# Temp_WiFi.net
KiCad netlist of a schematic drawn in EAGLE
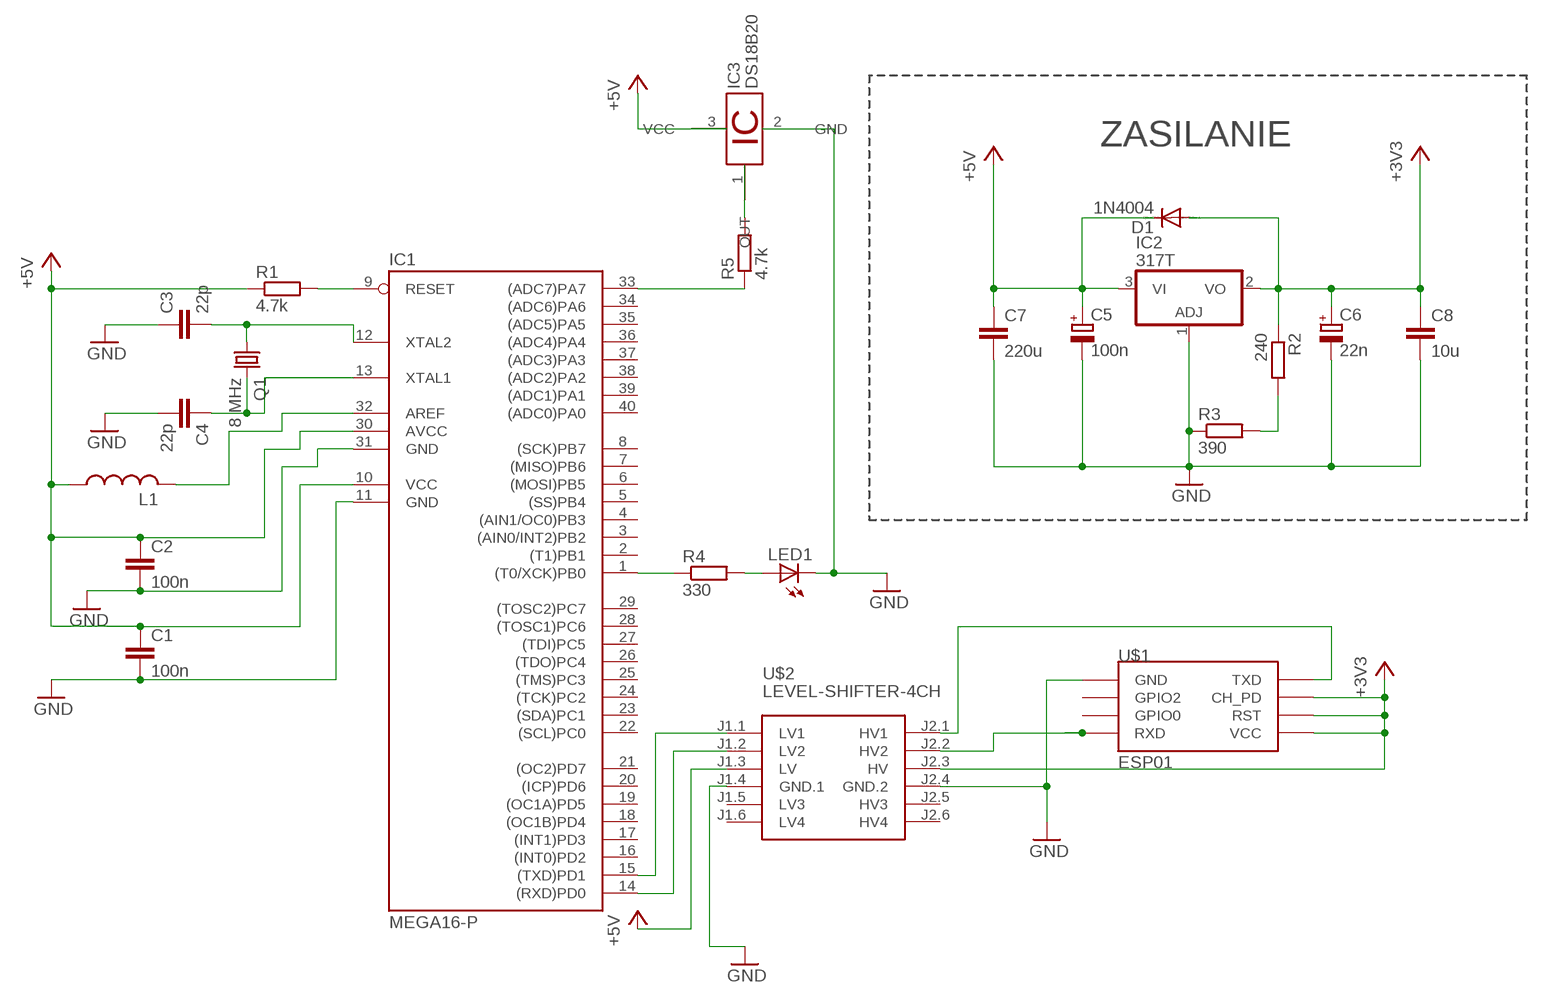
[diagram p0: schematic, sheet 1]

(export (version "E")
  (design (tool "Eeschema 10.0.6"))
  (components
    (comp (ref "C1")
      (value "100n")
      (footprint "eagle-import:C025-040X050")
      (libsource (lib "eagle-import") (part "C-EU025-040X050"))
    )
    (comp (ref "C2")
      (value "100n")
      (footprint "eagle-import:C025-040X050")
      (libsource (lib "eagle-import") (part "C-EU025-040X050"))
    )
    (comp (ref "C3")
      (value "22p")
      (footprint "eagle-import:C025-040X050")
      (libsource (lib "eagle-import") (part "C-EU025-040X050"))
    )
    (comp (ref "C4")
      (value "22p")
      (footprint "eagle-import:C025-040X050")
      (libsource (lib "eagle-import") (part "C-EU025-040X050"))
    )
    (comp (ref "C5")
      (value "100n")
      (footprint "eagle-import:E7,5-16")
      (libsource (lib "eagle-import") (part "CPOL-EUE7.5-16"))
    )
    (comp (ref "C6")
      (value "22n")
      (footprint "eagle-import:E7,5-16")
      (libsource (lib "eagle-import") (part "CPOL-EUE7.5-16"))
    )
    (comp (ref "C7")
      (value "220u")
      (footprint "eagle-import:C025-030X050")
      (libsource (lib "eagle-import") (part "C-EU025-030X050"))
    )
    (comp (ref "C8")
      (value "10u")
      (footprint "eagle-import:C025-030X050")
      (libsource (lib "eagle-import") (part "C-EU025-030X050"))
    )
    (comp (ref "D1")
      (value "1N4004")
      (footprint "eagle-import:DO41-10")
      (libsource (lib "eagle-import") (part "1N4004"))
    )
    (comp (ref "IC1")
      (value "MEGA16-P")
      (footprint "eagle-import:DIL40")
      (fields (field (name "MPN") "ATMEGA16-16PU"))
      (libsource (lib "eagle-import") (part "MEGA16-P"))
    )
    (comp (ref "IC2")
      (value "317T")
      (footprint "eagle-import:TO220H")
      (libsource (lib "eagle-import") (part "317T"))
    )
    (comp (ref "IC3")
      (value "DS18B20")
      (footprint "eagle-import:TO92-")
      (libsource (lib "eagle-import") (part "DS18B20"))
    )
    (comp (ref "L1")
      (value "L-US0204/7")
      (footprint "eagle-import:0204_7")
      (libsource (lib "eagle-import") (part "L-US0204/7"))
    )
    (comp (ref "LED1")
      (value "LED5MM")
      (footprint "eagle-import:LED5MM")
      (libsource (lib "eagle-import") (part "LED5MM"))
    )
    (comp (ref "Q1")
      (value "8 MHz")
      (footprint "eagle-import:HC49U-V")
      (libsource (lib "eagle-import") (part "CRYSTALHC49U-V"))
    )
    (comp (ref "R1")
      (value "4.7k")
      (footprint "eagle-import:0204_7")
      (libsource (lib "eagle-import") (part "R-EU_0204/7"))
    )
    (comp (ref "R2")
      (value "240")
      (footprint "eagle-import:0204_7")
      (libsource (lib "eagle-import") (part "R-EU_0204/7"))
    )
    (comp (ref "R3")
      (value "390")
      (footprint "eagle-import:0204_7")
      (libsource (lib "eagle-import") (part "R-EU_0204/7"))
    )
    (comp (ref "R4")
      (value "330")
      (footprint "eagle-import:0204_7")
      (libsource (lib "eagle-import") (part "R-EU_0204/7"))
    )
    (comp (ref "R5")
      (value "4.7k")
      (footprint "eagle-import:0204_7")
      (libsource (lib "eagle-import") (part "R-EU_0204/7"))
    )
    (comp (ref "U$1")
      (value "ESP01")
      (footprint "eagle-import:ESP01")
      (libsource (lib "eagle-import") (part "ESP01"))
    )
    (comp (ref "U$2")
      (value "LEVEL-SHIFTER-4CH")
      (footprint "eagle-import:LEVEL-SHIFTER-4CH")
      (libsource (lib "eagle-import") (part "LEVEL-SHIFTER-4CH"))
    )
  )
  (nets
    (net (code "1") (name "+3V3") (class "Default")
      (node (ref "C6") (pin "+") (pinfunction "+_+") (pintype "passive"))
      (node (ref "C8") (pin "1") (pinfunction "1_1") (pintype "passive"))
      (node (ref "D1") (pin "A") (pinfunction "A_A") (pintype "passive"))
      (node (ref "IC2") (pin "2") (pinfunction "VO_2") (pintype "passive"))
      (node (ref "R2") (pin "1") (pinfunction "1_1") (pintype "passive"))
      (node (ref "U$1") (pin "CH_PD") (pinfunction "CH_PD_CH_PD") (pintype "bidirectional"))
      (node (ref "U$1") (pin "RST") (pinfunction "RST_RST") (pintype "bidirectional"))
      (node (ref "U$1") (pin "VCC") (pinfunction "VCC_VCC") (pintype "bidirectional"))
      (node (ref "U$2") (pin "J2.3") (pinfunction "HV_J2.3") (pintype "power_in"))
    )
    (net (code "2") (name "+5V") (class "Default")
      (node (ref "C1") (pin "1") (pinfunction "1_1") (pintype "passive"))
      (node (ref "C2") (pin "1") (pinfunction "1_1") (pintype "passive"))
      (node (ref "C5") (pin "+") (pinfunction "+_+") (pintype "passive"))
      (node (ref "C7") (pin "1") (pinfunction "1_1") (pintype "passive"))
      (node (ref "D1") (pin "C") (pinfunction "C_C") (pintype "passive"))
      (node (ref "IC1") (pin "10") (pinfunction "VCC_10") (pintype "power_in"))
      (node (ref "IC1") (pin "30") (pinfunction "AVCC_30") (pintype "power_in"))
      (node (ref "IC2") (pin "3") (pinfunction "VI_3") (pintype "input"))
      (node (ref "IC3") (pin "3") (pinfunction "VCC_3") (pintype "bidirectional"))
      (node (ref "L1") (pin "1") (pinfunction "1_1") (pintype "passive"))
      (node (ref "R1") (pin "1") (pinfunction "1_1") (pintype "passive"))
      (node (ref "U$2") (pin "J1.3") (pinfunction "LV_J1.3") (pintype "power_in"))
    )
    (net (code "3") (name "/XTAL2") (class "Default")
      (node (ref "C3") (pin "2") (pinfunction "2_2") (pintype "passive"))
      (node (ref "C4") (pin "1") (pinfunction "1_1") (pintype "passive"))
      (node (ref "IC1") (pin "12") (pinfunction "XTAL2_12") (pintype "bidirectional"))
      (node (ref "IC1") (pin "13") (pinfunction "XTAL1_13") (pintype "bidirectional"))
      (node (ref "Q1") (pin "1") (pinfunction "1_1") (pintype "passive"))
      (node (ref "Q1") (pin "2") (pinfunction "2_2") (pintype "passive"))
    )
    (net (code "4") (name "GND") (class "Default")
      (node (ref "C1") (pin "2") (pinfunction "2_2") (pintype "passive"))
      (node (ref "C2") (pin "2") (pinfunction "2_2") (pintype "passive"))
      (node (ref "C3") (pin "1") (pinfunction "1_1") (pintype "passive"))
      (node (ref "C4") (pin "2") (pinfunction "2_2") (pintype "passive"))
      (node (ref "C5") (pin "-") (pinfunction "-_-") (pintype "passive"))
      (node (ref "C6") (pin "-") (pinfunction "-_-") (pintype "passive"))
      (node (ref "C7") (pin "2") (pinfunction "2_2") (pintype "passive"))
      (node (ref "C8") (pin "2") (pinfunction "2_2") (pintype "passive"))
      (node (ref "IC1") (pin "11") (pinfunction "GND_11") (pintype "power_in"))
      (node (ref "IC1") (pin "31") (pinfunction "GND_31") (pintype "power_in"))
      (node (ref "IC2") (pin "1") (pinfunction "ADJ_1") (pintype "input"))
      (node (ref "IC3") (pin "2") (pinfunction "GND_2") (pintype "bidirectional"))
      (node (ref "LED1") (pin "K") (pinfunction "C_K") (pintype "passive"))
      (node (ref "R3") (pin "1") (pinfunction "1_1") (pintype "passive"))
      (node (ref "U$1") (pin "GND") (pinfunction "GND_GND") (pintype "bidirectional"))
      (node (ref "U$2") (pin "J1.4") (pinfunction "GND.1_J1.4") (pintype "power_in"))
      (node (ref "U$2") (pin "J2.4") (pinfunction "GND.2_J2.4") (pintype "power_in"))
    )
    (net (code "5") (name "Net-(IC1-(ADC7)PA7)") (class "Default")
      (node (ref "IC1") (pin "33") (pinfunction "(ADC7)PA7_33") (pintype "bidirectional"))
      (node (ref "R5") (pin "1") (pinfunction "1_1") (pintype "passive"))
    )
    (net (code "6") (name "Net-(IC1-(RXD)PD0)") (class "Default")
      (node (ref "IC1") (pin "14") (pinfunction "(RXD)PD0_14") (pintype "bidirectional"))
      (node (ref "U$2") (pin "J1.2") (pinfunction "LV2_J1.2") (pintype "bidirectional"))
    )
    (net (code "7") (name "Net-(IC1-(T0{slash}XCK)PB0)") (class "Default")
      (node (ref "IC1") (pin "1") (pinfunction "(T0/XCK)PB0_1") (pintype "bidirectional"))
      (node (ref "R4") (pin "1") (pinfunction "1_1") (pintype "passive"))
    )
    (net (code "8") (name "Net-(IC1-(TXD)PD1)") (class "Default")
      (node (ref "IC1") (pin "15") (pinfunction "(TXD)PD1_15") (pintype "bidirectional"))
      (node (ref "U$2") (pin "J1.1") (pinfunction "LV1_J1.1") (pintype "bidirectional"))
    )
    (net (code "9") (name "Net-(IC1-AREF)") (class "Default")
      (node (ref "IC1") (pin "32") (pinfunction "AREF_32") (pintype "passive"))
      (node (ref "L1") (pin "2") (pinfunction "2_2") (pintype "passive"))
    )
    (net (code "10") (name "Net-(IC1-RESET)") (class "Default")
      (node (ref "IC1") (pin "9") (pinfunction "RESET_9") (pintype "input"))
      (node (ref "R1") (pin "2") (pinfunction "2_2") (pintype "passive"))
    )
    (net (code "11") (name "Net-(IC3-OUT)") (class "Default")
      (node (ref "IC3") (pin "1") (pinfunction "OUT_1") (pintype "bidirectional"))
      (node (ref "R5") (pin "2") (pinfunction "2_2") (pintype "passive"))
    )
    (net (code "12") (name "Net-(LED1-PadA)") (class "Default")
      (node (ref "LED1") (pin "A") (pinfunction "A_A") (pintype "passive"))
      (node (ref "R4") (pin "2") (pinfunction "2_2") (pintype "passive"))
    )
    (net (code "13") (name "Net-(R2-Pad2)") (class "Default")
      (node (ref "R2") (pin "2") (pinfunction "2_2") (pintype "passive"))
      (node (ref "R3") (pin "2") (pinfunction "2_2") (pintype "passive"))
    )
    (net (code "14") (name "Net-(U$1-RXD)") (class "Default")
      (node (ref "U$1") (pin "RX") (pinfunction "RXD_RX") (pintype "bidirectional"))
      (node (ref "U$2") (pin "J2.2") (pinfunction "HV2_J2.2") (pintype "bidirectional"))
    )
    (net (code "15") (name "Net-(U$1-TXD)") (class "Default")
      (node (ref "U$1") (pin "TX") (pinfunction "TXD_TX") (pintype "bidirectional"))
      (node (ref "U$2") (pin "J2.1") (pinfunction "HV1_J2.1") (pintype "bidirectional"))
    )
    (net (code "16") (name "unconnected-(IC1-(ADC0)PA0-Pad40)") (class "Default")
      (node (ref "IC1") (pin "40") (pinfunction "(ADC0)PA0_40") (pintype "bidirectional"))
    )
    (net (code "17") (name "unconnected-(IC1-(ADC1)PA1-Pad39)") (class "Default")
      (node (ref "IC1") (pin "39") (pinfunction "(ADC1)PA1_39") (pintype "bidirectional"))
    )
    (net (code "18") (name "unconnected-(IC1-(ADC2)PA2-Pad38)") (class "Default")
      (node (ref "IC1") (pin "38") (pinfunction "(ADC2)PA2_38") (pintype "bidirectional"))
    )
    (net (code "19") (name "unconnected-(IC1-(ADC3)PA3-Pad37)") (class "Default")
      (node (ref "IC1") (pin "37") (pinfunction "(ADC3)PA3_37") (pintype "bidirectional"))
    )
    (net (code "20") (name "unconnected-(IC1-(ADC4)PA4-Pad36)") (class "Default")
      (node (ref "IC1") (pin "36") (pinfunction "(ADC4)PA4_36") (pintype "bidirectional"))
    )
    (net (code "21") (name "unconnected-(IC1-(ADC5)PA5-Pad35)") (class "Default")
      (node (ref "IC1") (pin "35") (pinfunction "(ADC5)PA5_35") (pintype "bidirectional"))
    )
    (net (code "22") (name "unconnected-(IC1-(ADC6)PA6-Pad34)") (class "Default")
      (node (ref "IC1") (pin "34") (pinfunction "(ADC6)PA6_34") (pintype "bidirectional"))
    )
    (net (code "23") (name "unconnected-(IC1-(AIN0{slash}INT2)PB2-Pad3)") (class "Default")
      (node (ref "IC1") (pin "3") (pinfunction "(AIN0/INT2)PB2_3") (pintype "bidirectional"))
    )
    (net (code "24") (name "unconnected-(IC1-(AIN1{slash}OC0)PB3-Pad4)") (class "Default")
      (node (ref "IC1") (pin "4") (pinfunction "(AIN1/OC0)PB3_4") (pintype "bidirectional"))
    )
    (net (code "25") (name "unconnected-(IC1-(ICP)PD6-Pad20)") (class "Default")
      (node (ref "IC1") (pin "20") (pinfunction "(ICP)PD6_20") (pintype "bidirectional"))
    )
    (net (code "26") (name "unconnected-(IC1-(INT0)PD2-Pad16)") (class "Default")
      (node (ref "IC1") (pin "16") (pinfunction "(INT0)PD2_16") (pintype "bidirectional"))
    )
    (net (code "27") (name "unconnected-(IC1-(INT1)PD3-Pad17)") (class "Default")
      (node (ref "IC1") (pin "17") (pinfunction "(INT1)PD3_17") (pintype "bidirectional"))
    )
    (net (code "28") (name "unconnected-(IC1-(MISO)PB6-Pad7)") (class "Default")
      (node (ref "IC1") (pin "7") (pinfunction "(MISO)PB6_7") (pintype "bidirectional"))
    )
    (net (code "29") (name "unconnected-(IC1-(MOSI)PB5-Pad6)") (class "Default")
      (node (ref "IC1") (pin "6") (pinfunction "(MOSI)PB5_6") (pintype "bidirectional"))
    )
    (net (code "30") (name "unconnected-(IC1-(OC1A)PD5-Pad19)") (class "Default")
      (node (ref "IC1") (pin "19") (pinfunction "(OC1A)PD5_19") (pintype "bidirectional"))
    )
    (net (code "31") (name "unconnected-(IC1-(OC1B)PD4-Pad18)") (class "Default")
      (node (ref "IC1") (pin "18") (pinfunction "(OC1B)PD4_18") (pintype "bidirectional"))
    )
    (net (code "32") (name "unconnected-(IC1-(OC2)PD7-Pad21)") (class "Default")
      (node (ref "IC1") (pin "21") (pinfunction "(OC2)PD7_21") (pintype "bidirectional"))
    )
    (net (code "33") (name "unconnected-(IC1-(SCK)PB7-Pad8)") (class "Default")
      (node (ref "IC1") (pin "8") (pinfunction "(SCK)PB7_8") (pintype "bidirectional"))
    )
    (net (code "34") (name "unconnected-(IC1-(SCL)PC0-Pad22)") (class "Default")
      (node (ref "IC1") (pin "22") (pinfunction "(SCL)PC0_22") (pintype "bidirectional"))
    )
    (net (code "35") (name "unconnected-(IC1-(SDA)PC1-Pad23)") (class "Default")
      (node (ref "IC1") (pin "23") (pinfunction "(SDA)PC1_23") (pintype "bidirectional"))
    )
    (net (code "36") (name "unconnected-(IC1-(SS)PB4-Pad5)") (class "Default")
      (node (ref "IC1") (pin "5") (pinfunction "(SS)PB4_5") (pintype "bidirectional"))
    )
    (net (code "37") (name "unconnected-(IC1-(T1)PB1-Pad2)") (class "Default")
      (node (ref "IC1") (pin "2") (pinfunction "(T1)PB1_2") (pintype "bidirectional"))
    )
    (net (code "38") (name "unconnected-(IC1-(TCK)PC2-Pad24)") (class "Default")
      (node (ref "IC1") (pin "24") (pinfunction "(TCK)PC2_24") (pintype "bidirectional"))
    )
    (net (code "39") (name "unconnected-(IC1-(TDI)PC5-Pad27)") (class "Default")
      (node (ref "IC1") (pin "27") (pinfunction "(TDI)PC5_27") (pintype "bidirectional"))
    )
    (net (code "40") (name "unconnected-(IC1-(TDO)PC4-Pad26)") (class "Default")
      (node (ref "IC1") (pin "26") (pinfunction "(TDO)PC4_26") (pintype "bidirectional"))
    )
    (net (code "41") (name "unconnected-(IC1-(TMS)PC3-Pad25)") (class "Default")
      (node (ref "IC1") (pin "25") (pinfunction "(TMS)PC3_25") (pintype "bidirectional"))
    )
    (net (code "42") (name "unconnected-(IC1-(TOSC1)PC6-Pad28)") (class "Default")
      (node (ref "IC1") (pin "28") (pinfunction "(TOSC1)PC6_28") (pintype "bidirectional"))
    )
    (net (code "43") (name "unconnected-(IC1-(TOSC2)PC7-Pad29)") (class "Default")
      (node (ref "IC1") (pin "29") (pinfunction "(TOSC2)PC7_29") (pintype "bidirectional"))
    )
    (net (code "44") (name "unconnected-(U$1-PadGPIO0)") (class "Default")
      (node (ref "U$1") (pin "GPIO0") (pinfunction "GPIO0_GPIO0") (pintype "bidirectional"))
    )
    (net (code "45") (name "unconnected-(U$1-PadGPIO2)") (class "Default")
      (node (ref "U$1") (pin "GPIO2") (pinfunction "GPIO2_GPIO2") (pintype "bidirectional"))
    )
    (net (code "46") (name "unconnected-(U$2-HV3-PadJ2.5)") (class "Default")
      (node (ref "U$2") (pin "J2.5") (pinfunction "HV3_J2.5") (pintype "bidirectional"))
    )
    (net (code "47") (name "unconnected-(U$2-HV4-PadJ2.6)") (class "Default")
      (node (ref "U$2") (pin "J2.6") (pinfunction "HV4_J2.6") (pintype "bidirectional"))
    )
    (net (code "48") (name "unconnected-(U$2-LV3-PadJ1.5)") (class "Default")
      (node (ref "U$2") (pin "J1.5") (pinfunction "LV3_J1.5") (pintype "bidirectional"))
    )
    (net (code "49") (name "unconnected-(U$2-LV4-PadJ1.6)") (class "Default")
      (node (ref "U$2") (pin "J1.6") (pinfunction "LV4_J1.6") (pintype "bidirectional"))
    )
  )
)
